# ADC-PERIPHERALS.net
KiCad netlist of a schematic drawn in Altium Designer
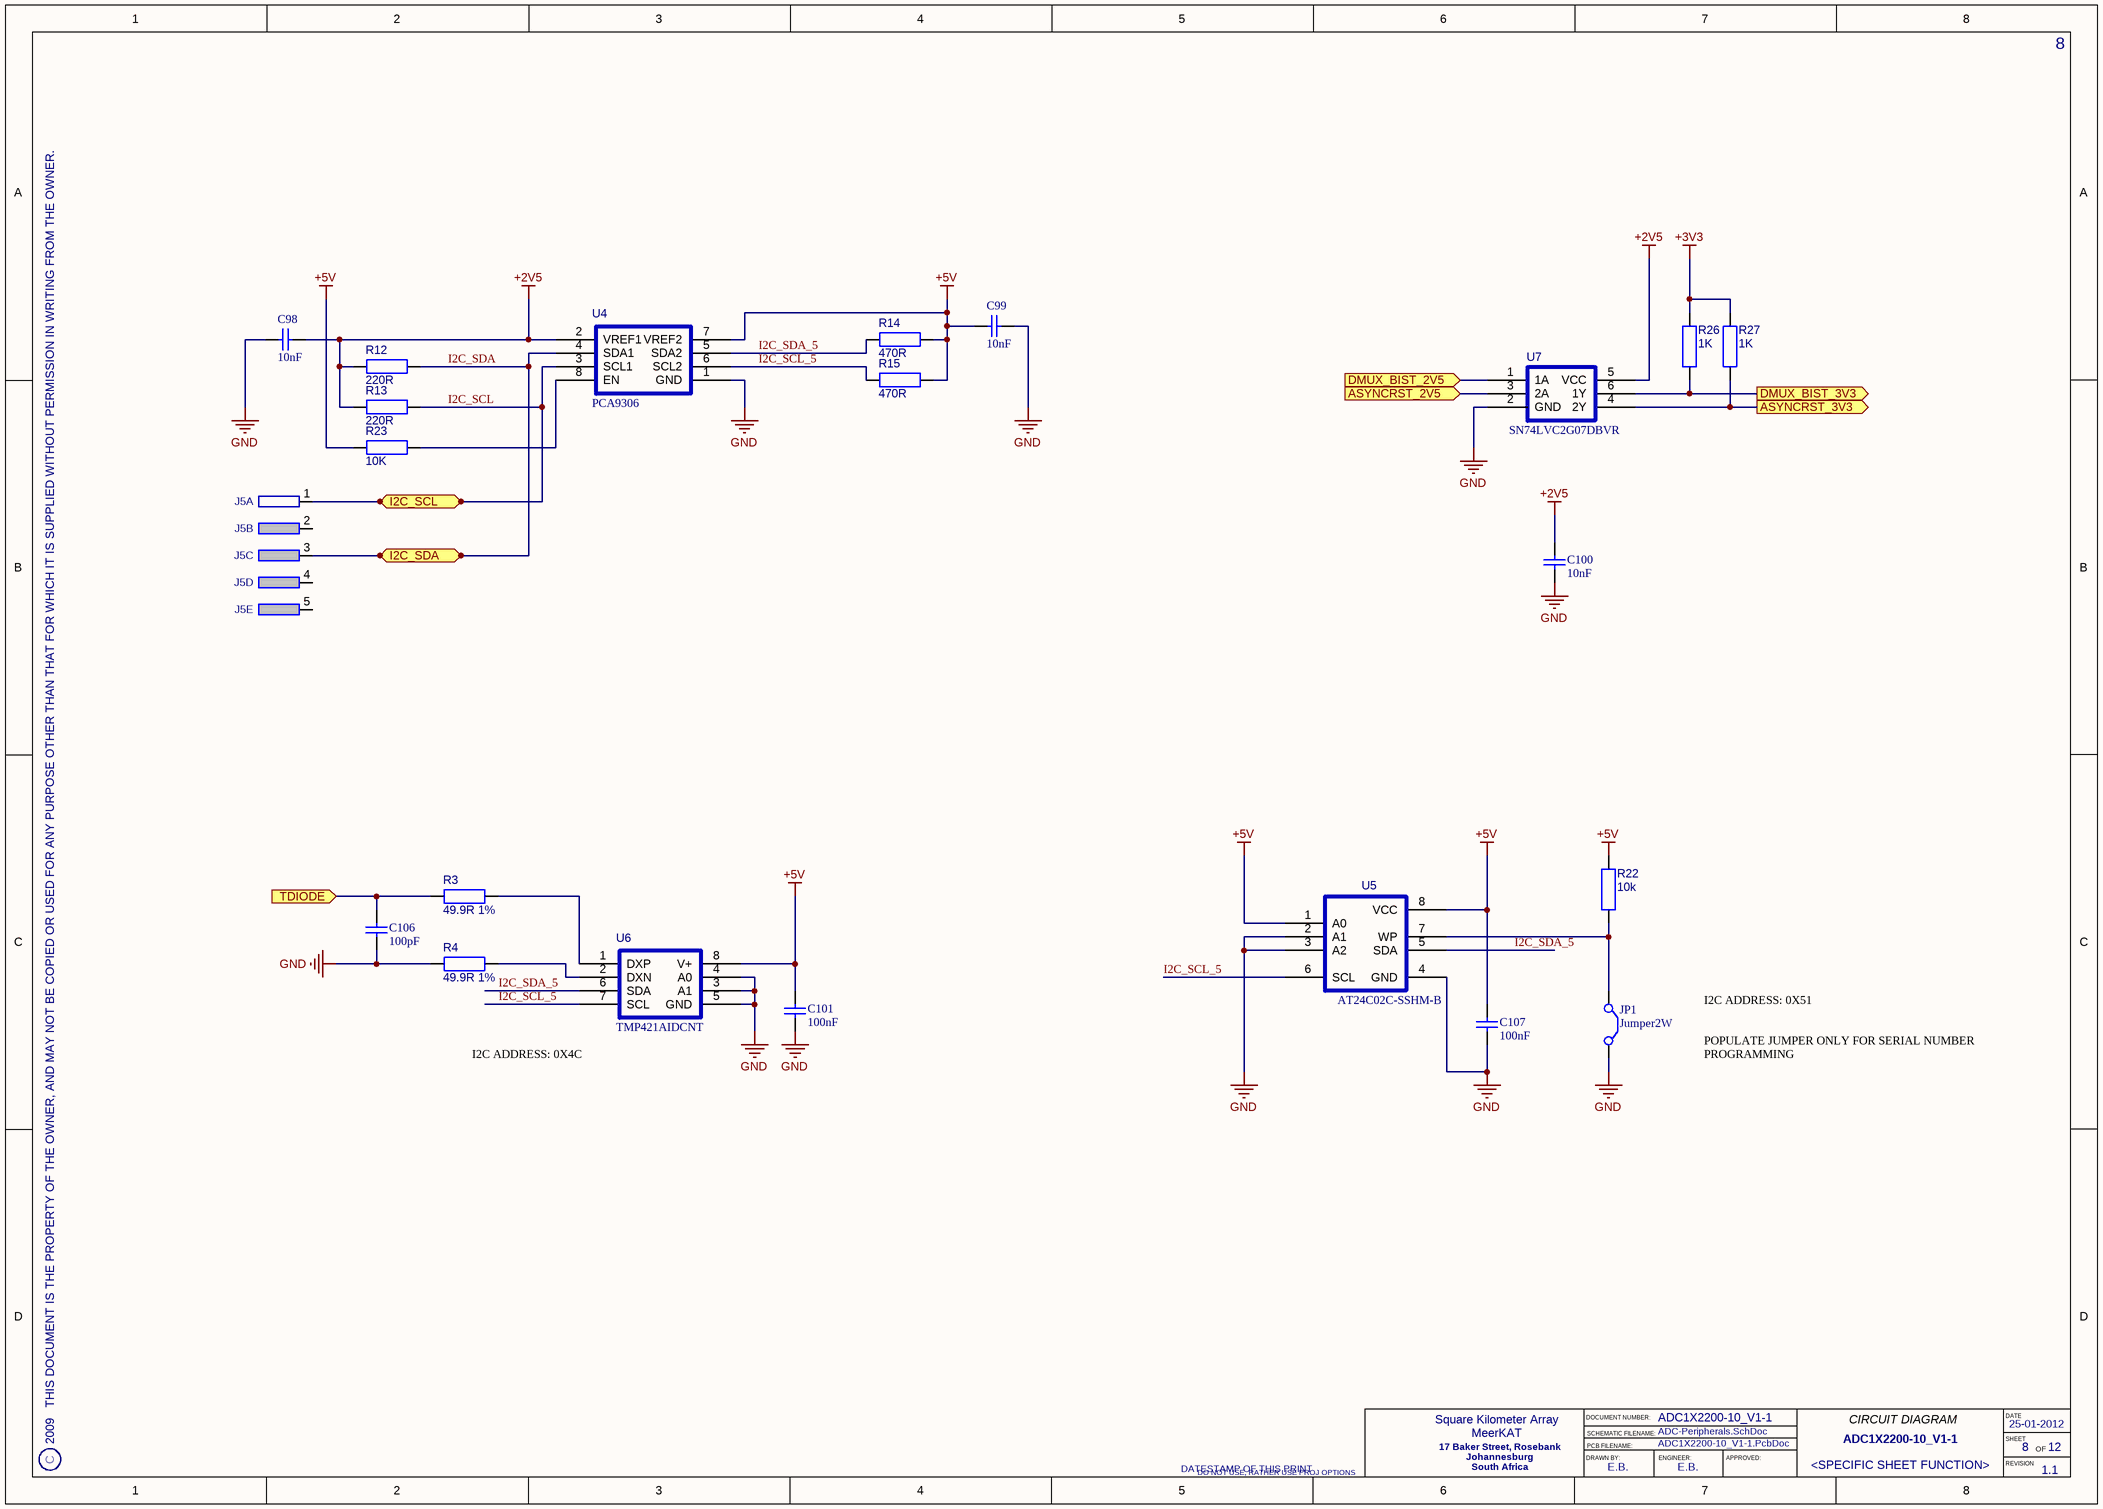
[diagram p0: ADC-PERIPHERALS.SchDoc]

(export (version "E")
  (design (tool "Eeschema 10.0.6"))
  (components
    (comp (ref "C98")
      (value "10nF")
      (footprint "CAPC1005X55N")
      (description "Capacitor 0402 SMD")
      (fields (field (name "CREATED_BY") "EDA-ASA") (field (name "CHECKED_BY") "*"))
      (libsource (lib "EDA-Passive") (part "cap0402"))
    )
    (comp (ref "C99")
      (value "10nF")
      (footprint "CAPC1005X55N")
      (description "Capacitor 0402 SMD")
      (fields (field (name "CREATED_BY") "EDA-ASA") (field (name "CHECKED_BY") "*"))
      (libsource (lib "EDA-Passive") (part "cap0402"))
    )
    (comp (ref "C100")
      (value "10nF")
      (footprint "CAPC1005X55N")
      (description "Capacitor 0402 SMD")
      (fields (field (name "CREATED_BY") "EDA-ASA") (field (name "CHECKED_BY") "*"))
      (libsource (lib "EDA-Passive") (part "cap0402"))
    )
    (comp (ref "C101")
      (value "100nF")
      (footprint "CAPC1005X55N")
      (description "Capacitor 0402 SMD")
      (fields (field (name "CREATED_BY") "EDA-ASA") (field (name "CHECKED_BY") "*"))
      (libsource (lib "EDA-Passive") (part "cap0402"))
    )
    (comp (ref "C106")
      (value "100pF")
      (footprint "CAPC1005X55N")
      (description "Capacitor 0402 SMD")
      (fields (field (name "CREATED_BY") "EDA-ASA") (field (name "CHECKED_BY") "*"))
      (libsource (lib "EDA-Passive") (part "cap0402"))
    )
    (comp (ref "C107")
      (value "100nF")
      (footprint "CAPC1005X55N")
      (description "Capacitor 0402 SMD")
      (fields (field (name "CREATED_BY") "EDA-ASA") (field (name "CHECKED_BY") "*"))
      (libsource (lib "EDA-Passive") (part "cap0402"))
    )
    (comp (ref "J5")
      (value "SAMTEC-TSM-105-01-TM-SV-5W-HDR")
      (footprint "TSM_5X1_SV")
      (libsource (lib "Ish") (part "SAMTEC-TSM-105-01-TM-SV-5W-HDR"))
    )
    (comp (ref "JP1")
      (value "Jumper2W")
      (footprint "JP-100MIL")
      (description "Jumper Wire")
      (fields (field (name "PUBLISHER") "Altium Limited"))
      (libsource (lib "EDA-Hardware") (part "Jumper2W"))
    )
    (comp (ref "R3")
      (value "49.9R 1%")
      (footprint "0603")
      (description "RESISTOR SMD 0603")
      (fields (field (name "CREATED_BY") "*") (field (name "CHECKED_BY") "NN"))
      (libsource (lib "EDA_Passive") (part "RES-0805"))
    )
    (comp (ref "R4")
      (value "49.9R 1%")
      (footprint "0603")
      (description "RESISTOR SMD 0603")
      (fields (field (name "CREATED_BY") "*") (field (name "CHECKED_BY") "NN"))
      (libsource (lib "EDA_Passive") (part "RES-0805"))
    )
    (comp (ref "R12")
      (value "220R")
      (footprint "0603")
      (description "RESISTOR SMD 0603")
      (fields (field (name "CREATED_BY") "*") (field (name "CHECKED_BY") "NN"))
      (libsource (lib "EDA_Passive") (part "RES-0805"))
    )
    (comp (ref "R13")
      (value "220R")
      (footprint "0603")
      (description "RESISTOR SMD 0603")
      (fields (field (name "CREATED_BY") "*") (field (name "CHECKED_BY") "NN"))
      (libsource (lib "EDA_Passive") (part "RES-0805"))
    )
    (comp (ref "R14")
      (value "470R")
      (footprint "0603")
      (description "RESISTOR SMD 0603")
      (fields (field (name "CREATED_BY") "*") (field (name "CHECKED_BY") "NN"))
      (libsource (lib "EDA_Passive") (part "RES-0805"))
    )
    (comp (ref "R15")
      (value "470R")
      (footprint "0603")
      (description "RESISTOR SMD 0603")
      (fields (field (name "CREATED_BY") "*") (field (name "CHECKED_BY") "NN"))
      (libsource (lib "EDA_Passive") (part "RES-0805"))
    )
    (comp (ref "R22")
      (value "10k")
      (footprint "0603")
      (description "RESISTOR SMD 0603")
      (fields (field (name "CREATED_BY") "*") (field (name "CHECKED_BY") "NN"))
      (libsource (lib "EDA_Passive") (part "RES-0805"))
    )
    (comp (ref "R23")
      (value "10K")
      (footprint "0603")
      (description "RESISTOR SMD 0603")
      (fields (field (name "CREATED_BY") "*") (field (name "CHECKED_BY") "NN"))
      (libsource (lib "EDA_Passive") (part "RES-0805"))
    )
    (comp (ref "R26")
      (value "1K")
      (footprint "0603")
      (description "RESISTOR SMD 0603")
      (fields (field (name "CREATED_BY") "*") (field (name "CHECKED_BY") "NN"))
      (libsource (lib "EDA_Passive") (part "RES-0805"))
    )
    (comp (ref "R27")
      (value "1K")
      (footprint "0603")
      (description "RESISTOR SMD 0603")
      (fields (field (name "CREATED_BY") "*") (field (name "CHECKED_BY") "NN"))
      (libsource (lib "EDA_Passive") (part "RES-0805"))
    )
    (comp (ref "U4")
      (value "PCA9306")
      (footprint "SOP65P400X130-8USR")
      (description "Dual Bidirectional I2C Bus and SMBus Voltage-Level Translator")
      (fields
        (field (name "MANUFACTURER") "TI")
        (field (name "CREATED_BY") "IN")
        (field (name "CHECKED_BY") "*")
      )
      (libsource (lib "Ishvah-TEMP") (part "PCA9306DCTR"))
    )
    (comp (ref "U5")
      (value "AT24C02C-SSHM-B")
      (footprint "SOIC127P600X175-8N")
      (description "Two wire Serial EEPROM 2K (256 x 8)")
      (fields
        (field (name "MANUFACTURER") "Atmel")
        (field (name "CREATED_BY") "IN")
        (field (name "CHECKED_BY") "*")
      )
      (libsource (lib "Ishvah-TEMP") (part "AT24C02B"))
    )
    (comp (ref "U6")
      (value "TMP421AIDCNT")
      (footprint "TI_SOT23-8")
      (description "Remote and Local TempreatureSensor in SOT23-8")
      (fields
        (field (name "MANUFACTURER") "TI")
        (field (name "CREATED_BY") "IN")
        (field (name "CHECKED_BY") "*")
      )
      (libsource (lib "Ishvah-TEMP") (part "TMP421AIDCNT"))
    )
    (comp (ref "U7")
      (value "SN74LVC2G07DBVR")
      (footprint "SOT95P280X145-6N")
      (description "Dual Buffer/Driver with open-drain output")
      (fields
        (field (name "MANUFACTURER") "TI")
        (field (name "CREATED_BY") "IN")
        (field (name "CHECKED_BY") "*")
      )
      (libsource (lib "Ishvah-TEMP") (part "SN74LVC2G07DBVR"))
    )
  )
  (nets
    (net (code "1") (name "+2V5") (class "Default")
      (node (ref "C100") (pin "2") (pinfunction "2_2") (pintype "passive"))
      (node (ref "C98") (pin "2") (pinfunction "2_2") (pintype "passive"))
      (node (ref "R12") (pin "1") (pinfunction "1_1") (pintype "passive"))
      (node (ref "R13") (pin "1") (pinfunction "1_1") (pintype "passive"))
      (node (ref "U4") (pin "2") (pinfunction "VREF1_2") (pintype "passive"))
      (node (ref "U7") (pin "5") (pinfunction "VCC_5") (pintype "passive"))
    )
    (net (code "2") (name "+3V3") (class "Default")
      (node (ref "R26") (pin "1") (pinfunction "1_1") (pintype "passive"))
      (node (ref "R27") (pin "1") (pinfunction "1_1") (pintype "passive"))
    )
    (net (code "3") (name "+5V") (class "Default")
      (node (ref "C101") (pin "2") (pinfunction "2_2") (pintype "passive"))
      (node (ref "C107") (pin "2") (pinfunction "2_2") (pintype "passive"))
      (node (ref "C99") (pin "1") (pinfunction "1_1") (pintype "passive"))
      (node (ref "R14") (pin "2") (pinfunction "2_2") (pintype "passive"))
      (node (ref "R15") (pin "2") (pinfunction "2_2") (pintype "passive"))
      (node (ref "R22") (pin "1") (pinfunction "1_1") (pintype "passive"))
      (node (ref "R23") (pin "2") (pinfunction "2_2") (pintype "passive"))
      (node (ref "U4") (pin "7") (pinfunction "VREF2_7") (pintype "passive"))
      (node (ref "U5") (pin "1") (pinfunction "A0_1") (pintype "passive"))
      (node (ref "U5") (pin "8") (pinfunction "VCC_8") (pintype "passive"))
      (node (ref "U6") (pin "8") (pinfunction "V+_8") (pintype "passive"))
    )
    (net (code "4") (name "/ASYNCRST_2V5") (class "Default")
      (node (ref "U7") (pin "3") (pinfunction "2A_3") (pintype "passive"))
    )
    (net (code "5") (name "/ASYNCRST_3V3") (class "Default")
      (node (ref "R27") (pin "2") (pinfunction "2_2") (pintype "passive"))
      (node (ref "U7") (pin "4") (pinfunction "2Y_4") (pintype "passive"))
    )
    (net (code "6") (name "/DMUX_BIST_2V5") (class "Default")
      (node (ref "U7") (pin "1") (pinfunction "1A_1") (pintype "passive"))
    )
    (net (code "7") (name "/DMUX_BIST_3V3") (class "Default")
      (node (ref "R26") (pin "2") (pinfunction "2_2") (pintype "passive"))
      (node (ref "U7") (pin "6") (pinfunction "1Y_6") (pintype "passive"))
    )
    (net (code "8") (name "/I2C_SCL") (class "Default")
      (node (ref "J5") (pin "1") (pintype "passive"))
      (node (ref "R13") (pin "2") (pinfunction "2_2") (pintype "passive"))
      (node (ref "U4") (pin "3") (pinfunction "SCL1_3") (pintype "passive"))
    )
    (net (code "9") (name "/I2C_SCL_5") (class "Default")
      (node (ref "R15") (pin "1") (pinfunction "1_1") (pintype "passive"))
      (node (ref "U4") (pin "6") (pinfunction "SCL2_6") (pintype "passive"))
      (node (ref "U5") (pin "6") (pinfunction "SCL_6") (pintype "passive"))
      (node (ref "U6") (pin "7") (pinfunction "SCL_7") (pintype "passive"))
    )
    (net (code "10") (name "/I2C_SDA") (class "Default")
      (node (ref "J5") (pin "3") (pintype "passive"))
      (node (ref "R12") (pin "2") (pinfunction "2_2") (pintype "passive"))
      (node (ref "U4") (pin "4") (pinfunction "SDA1_4") (pintype "passive"))
    )
    (net (code "11") (name "/I2C_SDA_5") (class "Default")
      (node (ref "R14") (pin "1") (pinfunction "1_1") (pintype "passive"))
      (node (ref "U4") (pin "5") (pinfunction "SDA2_5") (pintype "passive"))
      (node (ref "U5") (pin "5") (pinfunction "SDA_5") (pintype "passive"))
      (node (ref "U6") (pin "6") (pinfunction "SDA_6") (pintype "passive"))
    )
    (net (code "12") (name "/TDIODE") (class "Default")
      (node (ref "C106") (pin "2") (pinfunction "2_2") (pintype "passive"))
      (node (ref "R3") (pin "1") (pinfunction "1_1") (pintype "passive"))
    )
    (net (code "13") (name "GND") (class "Default")
      (node (ref "C100") (pin "1") (pinfunction "1_1") (pintype "passive"))
      (node (ref "C101") (pin "1") (pinfunction "1_1") (pintype "passive"))
      (node (ref "C106") (pin "1") (pinfunction "1_1") (pintype "passive"))
      (node (ref "C107") (pin "1") (pinfunction "1_1") (pintype "passive"))
      (node (ref "C98") (pin "1") (pinfunction "1_1") (pintype "passive"))
      (node (ref "C99") (pin "2") (pinfunction "2_2") (pintype "passive"))
      (node (ref "JP1") (pin "2") (pinfunction "C2_2") (pintype "passive"))
      (node (ref "R4") (pin "1") (pinfunction "1_1") (pintype "passive"))
      (node (ref "U4") (pin "1") (pinfunction "GND_1") (pintype "passive"))
      (node (ref "U5") (pin "2") (pinfunction "A1_2") (pintype "passive"))
      (node (ref "U5") (pin "3") (pinfunction "A2_3") (pintype "passive"))
      (node (ref "U5") (pin "4") (pinfunction "GND_4") (pintype "power_in"))
      (node (ref "U6") (pin "3") (pinfunction "A1_3") (pintype "passive"))
      (node (ref "U6") (pin "4") (pinfunction "A0_4") (pintype "passive"))
      (node (ref "U6") (pin "5") (pinfunction "GND_5") (pintype "passive"))
      (node (ref "U7") (pin "2") (pinfunction "GND_2") (pintype "passive"))
    )
    (net (code "14") (name "Net-(JP1-C1)") (class "Default")
      (node (ref "JP1") (pin "1") (pinfunction "C1_1") (pintype "passive"))
      (node (ref "R22") (pin "2") (pinfunction "2_2") (pintype "passive"))
      (node (ref "U5") (pin "7") (pinfunction "WP_7") (pintype "passive"))
    )
    (net (code "15") (name "Net-(U4-EN)") (class "Default")
      (node (ref "R23") (pin "1") (pinfunction "1_1") (pintype "passive"))
      (node (ref "U4") (pin "8") (pinfunction "EN_8") (pintype "passive"))
    )
    (net (code "16") (name "Net-(U6-DXN)") (class "Default")
      (node (ref "R4") (pin "2") (pinfunction "2_2") (pintype "passive"))
      (node (ref "U6") (pin "2") (pinfunction "DXN_2") (pintype "passive"))
    )
    (net (code "17") (name "Net-(U6-DXP)") (class "Default")
      (node (ref "R3") (pin "2") (pinfunction "2_2") (pintype "passive"))
      (node (ref "U6") (pin "1") (pinfunction "DXP_1") (pintype "passive"))
    )
    (net (code "18") (name "unconnected-(J5-Pad2)") (class "Default")
      (node (ref "J5") (pin "2") (pintype "passive"))
    )
    (net (code "19") (name "unconnected-(J5-Pad4)") (class "Default")
      (node (ref "J5") (pin "4") (pintype "passive"))
    )
    (net (code "20") (name "unconnected-(J5-Pad5)") (class "Default")
      (node (ref "J5") (pin "5") (pintype "passive"))
    )
  )
)
